# Sheet1.net
KiCad netlist of a schematic drawn in Altium Designer
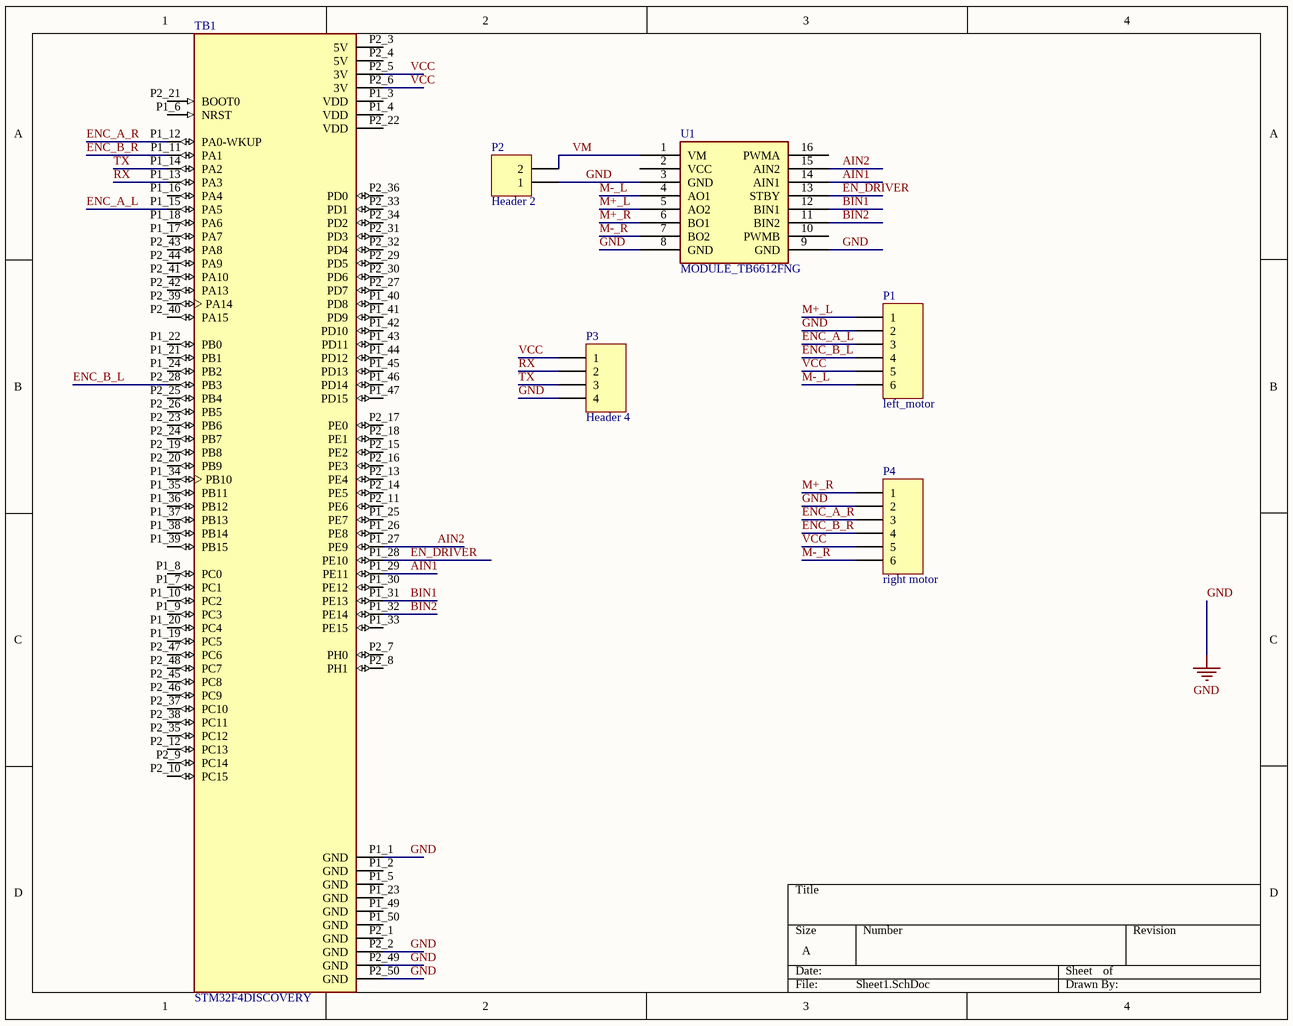
[diagram p0: Sheet1.SchDoc]

(export (version "E")
  (design (tool "Eeschema 10.0.6"))
  (components
    (comp (ref "P1")
      (value "left_motor")
      (footprint "HDR1X6")
      (description "Header, 6-Pin")
      (fields (field (name "PUBLISHER") "Altium Limited"))
      (libsource (lib "Miscellaneous Connectors") (part "Header 6"))
    )
    (comp (ref "P2")
      (value "Header 2")
      (footprint "HDR1X2")
      (description "Header, 2-Pin")
      (fields (field (name "PUBLISHER") "Altium Limited"))
      (libsource (lib "Miscellaneous Connectors") (part "Header 2"))
    )
    (comp (ref "P3")
      (value "Header 4")
      (footprint "HDR1X4")
      (description "Header, 4-Pin")
      (fields (field (name "PUBLISHER") "Altium Limited"))
      (libsource (lib "Miscellaneous Connectors") (part "Header 4"))
    )
    (comp (ref "P4")
      (value "right motor")
      (footprint "HDR1X6")
      (description "Header, 6-Pin")
      (fields (field (name "PUBLISHER") "Altium Limited"))
      (libsource (lib "Miscellaneous Connectors") (part "Header 6"))
    )
    (comp (ref "TB1")
      (value "STM32F4DISCOVERY")
      (footprint "MODULE_STM32F4DISCOVERY")
      (description "Development kit: ARM ST; pin strips, pin header; No.of")
      (libsource (lib "STM32F4DISCOVERY") (part "STM32F4DISCOVERY"))
    )
    (comp (ref "U1")
      (value "MODULE_TB6612FNG")
      (footprint "MODULE_TB6612FNG")
      (description "Module Dual Motor Driver 2.5-13.5V 3.2A Peak 21x18mm")
      (libsource (lib "Motor Drivers") (part "MODULE_TB6612FNG"))
    )
  )
  (nets
    (net (code "1") (name "/AIN1") (class "Default")
      (node (ref "TB1") (pin "P1_29") (pinfunction "PE11_P1_29") (pintype "bidirectional"))
      (node (ref "U1") (pin "14") (pinfunction "AIN1_14") (pintype "passive"))
    )
    (net (code "2") (name "/AIN2") (class "Default")
      (node (ref "TB1") (pin "P1_27") (pinfunction "PE9_P1_27") (pintype "bidirectional"))
      (node (ref "U1") (pin "15") (pinfunction "AIN2_15") (pintype "passive"))
    )
    (net (code "3") (name "/BIN1") (class "Default")
      (node (ref "TB1") (pin "P1_31") (pinfunction "PE13_P1_31") (pintype "bidirectional"))
      (node (ref "U1") (pin "12") (pinfunction "BIN1_12") (pintype "passive"))
    )
    (net (code "4") (name "/BIN2") (class "Default")
      (node (ref "TB1") (pin "P1_32") (pinfunction "PE14_P1_32") (pintype "bidirectional"))
      (node (ref "U1") (pin "11") (pinfunction "BIN2_11") (pintype "passive"))
    )
    (net (code "5") (name "/ENC_A_L") (class "Default")
      (node (ref "P1") (pin "3") (pinfunction "3_3") (pintype "passive"))
      (node (ref "TB1") (pin "P1_15") (pinfunction "PA5_P1_15") (pintype "bidirectional"))
    )
    (net (code "6") (name "/ENC_A_R") (class "Default")
      (node (ref "P4") (pin "3") (pinfunction "3_3") (pintype "passive"))
      (node (ref "TB1") (pin "P1_12") (pinfunction "PA0-WKUP_P1_12") (pintype "bidirectional"))
    )
    (net (code "7") (name "/ENC_B_L") (class "Default")
      (node (ref "P1") (pin "4") (pinfunction "4_4") (pintype "passive"))
      (node (ref "TB1") (pin "P2_28") (pinfunction "PB3_P2_28") (pintype "bidirectional"))
    )
    (net (code "8") (name "/ENC_B_R") (class "Default")
      (node (ref "P4") (pin "4") (pinfunction "4_4") (pintype "passive"))
      (node (ref "TB1") (pin "P1_11") (pinfunction "PA1_P1_11") (pintype "bidirectional"))
    )
    (net (code "9") (name "/EN_DRIVER") (class "Default")
      (node (ref "TB1") (pin "P1_28") (pinfunction "PE10_P1_28") (pintype "bidirectional"))
      (node (ref "U1") (pin "13") (pinfunction "STBY_13") (pintype "passive"))
    )
    (net (code "10") (name "/M+_L") (class "Default")
      (node (ref "P1") (pin "1") (pinfunction "1_1") (pintype "passive"))
      (node (ref "U1") (pin "5") (pinfunction "AO2_5") (pintype "passive"))
    )
    (net (code "11") (name "/M+_R") (class "Default")
      (node (ref "P4") (pin "1") (pinfunction "1_1") (pintype "passive"))
      (node (ref "U1") (pin "6") (pinfunction "BO1_6") (pintype "passive"))
    )
    (net (code "12") (name "/M-_L") (class "Default")
      (node (ref "P1") (pin "6") (pinfunction "6_6") (pintype "passive"))
      (node (ref "U1") (pin "4") (pinfunction "AO1_4") (pintype "passive"))
    )
    (net (code "13") (name "/M-_R") (class "Default")
      (node (ref "P4") (pin "6") (pinfunction "6_6") (pintype "passive"))
      (node (ref "U1") (pin "7") (pinfunction "BO2_7") (pintype "passive"))
    )
    (net (code "14") (name "/RX") (class "Default")
      (node (ref "P3") (pin "2") (pinfunction "2_2") (pintype "passive"))
      (node (ref "TB1") (pin "P1_13") (pinfunction "PA3_P1_13") (pintype "bidirectional"))
    )
    (net (code "15") (name "/TX") (class "Default")
      (node (ref "P3") (pin "3") (pinfunction "3_3") (pintype "passive"))
      (node (ref "TB1") (pin "P1_14") (pinfunction "PA2_P1_14") (pintype "bidirectional"))
    )
    (net (code "16") (name "/VCC") (class "Default")
      (node (ref "P1") (pin "5") (pinfunction "5_5") (pintype "passive"))
      (node (ref "P3") (pin "1") (pinfunction "1_1") (pintype "passive"))
      (node (ref "P4") (pin "5") (pinfunction "5_5") (pintype "passive"))
      (node (ref "TB1") (pin "P2_5") (pinfunction "3V_P2_5") (pintype "power_in"))
      (node (ref "TB1") (pin "P2_6") (pinfunction "3V_P2_6") (pintype "power_in"))
    )
    (net (code "17") (name "/VM") (class "Default")
      (node (ref "P2") (pin "2") (pinfunction "2_2") (pintype "passive"))
      (node (ref "U1") (pin "1") (pinfunction "VM_1") (pintype "passive"))
    )
    (net (code "18") (name "GND") (class "Default")
      (node (ref "P1") (pin "2") (pinfunction "2_2") (pintype "passive"))
      (node (ref "P2") (pin "1") (pinfunction "1_1") (pintype "passive"))
      (node (ref "P3") (pin "4") (pinfunction "4_4") (pintype "passive"))
      (node (ref "P4") (pin "2") (pinfunction "2_2") (pintype "passive"))
      (node (ref "TB1") (pin "P1_1") (pinfunction "GND_P1_1") (pintype "power_in"))
      (node (ref "TB1") (pin "P2_2") (pinfunction "GND_P2_2") (pintype "power_in"))
      (node (ref "TB1") (pin "P2_49") (pinfunction "GND_P2_49") (pintype "power_in"))
      (node (ref "TB1") (pin "P2_50") (pinfunction "GND_P2_50") (pintype "power_in"))
      (node (ref "U1") (pin "3") (pinfunction "GND_3") (pintype "passive"))
      (node (ref "U1") (pin "8") (pinfunction "GND_8") (pintype "passive"))
      (node (ref "U1") (pin "9") (pinfunction "GND_9") (pintype "passive"))
    )
    (net (code "19") (name "unconnected-(TB1-5V-PadP2_3)") (class "Default")
      (node (ref "TB1") (pin "P2_3") (pinfunction "5V_P2_3") (pintype "power_in"))
    )
    (net (code "20") (name "unconnected-(TB1-5V-PadP2_4)") (class "Default")
      (node (ref "TB1") (pin "P2_4") (pinfunction "5V_P2_4") (pintype "power_in"))
    )
    (net (code "21") (name "unconnected-(TB1-BOOT0-PadP2_21)") (class "Default")
      (node (ref "TB1") (pin "P2_21") (pinfunction "BOOT0_P2_21") (pintype "input"))
    )
    (net (code "22") (name "unconnected-(TB1-GND-PadP1_2)") (class "Default")
      (node (ref "TB1") (pin "P1_2") (pinfunction "GND_P1_2") (pintype "power_in"))
    )
    (net (code "23") (name "unconnected-(TB1-GND-PadP1_5)") (class "Default")
      (node (ref "TB1") (pin "P1_5") (pinfunction "GND_P1_5") (pintype "power_in"))
    )
    (net (code "24") (name "unconnected-(TB1-GND-PadP1_23)") (class "Default")
      (node (ref "TB1") (pin "P1_23") (pinfunction "GND_P1_23") (pintype "power_in"))
    )
    (net (code "25") (name "unconnected-(TB1-GND-PadP1_49)") (class "Default")
      (node (ref "TB1") (pin "P1_49") (pinfunction "GND_P1_49") (pintype "power_in"))
    )
    (net (code "26") (name "unconnected-(TB1-GND-PadP1_50)") (class "Default")
      (node (ref "TB1") (pin "P1_50") (pinfunction "GND_P1_50") (pintype "power_in"))
    )
    (net (code "27") (name "unconnected-(TB1-GND-PadP2_1)") (class "Default")
      (node (ref "TB1") (pin "P2_1") (pinfunction "GND_P2_1") (pintype "power_in"))
    )
    (net (code "28") (name "unconnected-(TB1-NRST-PadP1_6)") (class "Default")
      (node (ref "TB1") (pin "P1_6") (pinfunction "NRST_P1_6") (pintype "input"))
    )
    (net (code "29") (name "unconnected-(TB1-PA4-PadP1_16)") (class "Default")
      (node (ref "TB1") (pin "P1_16") (pinfunction "PA4_P1_16") (pintype "bidirectional"))
    )
    (net (code "30") (name "unconnected-(TB1-PA6-PadP1_18)") (class "Default")
      (node (ref "TB1") (pin "P1_18") (pinfunction "PA6_P1_18") (pintype "bidirectional"))
    )
    (net (code "31") (name "unconnected-(TB1-PA7-PadP1_17)") (class "Default")
      (node (ref "TB1") (pin "P1_17") (pinfunction "PA7_P1_17") (pintype "bidirectional"))
    )
    (net (code "32") (name "unconnected-(TB1-PA8-PadP2_43)") (class "Default")
      (node (ref "TB1") (pin "P2_43") (pinfunction "PA8_P2_43") (pintype "bidirectional"))
    )
    (net (code "33") (name "unconnected-(TB1-PA9-PadP2_44)") (class "Default")
      (node (ref "TB1") (pin "P2_44") (pinfunction "PA9_P2_44") (pintype "bidirectional"))
    )
    (net (code "34") (name "unconnected-(TB1-PA10-PadP2_41)") (class "Default")
      (node (ref "TB1") (pin "P2_41") (pinfunction "PA10_P2_41") (pintype "bidirectional"))
    )
    (net (code "35") (name "unconnected-(TB1-PA13-PadP2_42)") (class "Default")
      (node (ref "TB1") (pin "P2_42") (pinfunction "PA13_P2_42") (pintype "bidirectional"))
    )
    (net (code "36") (name "unconnected-(TB1-PA14-PadP2_39)") (class "Default")
      (node (ref "TB1") (pin "P2_39") (pinfunction "PA14_P2_39") (pintype "bidirectional"))
    )
    (net (code "37") (name "unconnected-(TB1-PA15-PadP2_40)") (class "Default")
      (node (ref "TB1") (pin "P2_40") (pinfunction "PA15_P2_40") (pintype "bidirectional"))
    )
    (net (code "38") (name "unconnected-(TB1-PB0-PadP1_22)") (class "Default")
      (node (ref "TB1") (pin "P1_22") (pinfunction "PB0_P1_22") (pintype "bidirectional"))
    )
    (net (code "39") (name "unconnected-(TB1-PB1-PadP1_21)") (class "Default")
      (node (ref "TB1") (pin "P1_21") (pinfunction "PB1_P1_21") (pintype "bidirectional"))
    )
    (net (code "40") (name "unconnected-(TB1-PB2-PadP1_24)") (class "Default")
      (node (ref "TB1") (pin "P1_24") (pinfunction "PB2_P1_24") (pintype "bidirectional"))
    )
    (net (code "41") (name "unconnected-(TB1-PB4-PadP2_25)") (class "Default")
      (node (ref "TB1") (pin "P2_25") (pinfunction "PB4_P2_25") (pintype "bidirectional"))
    )
    (net (code "42") (name "unconnected-(TB1-PB5-PadP2_26)") (class "Default")
      (node (ref "TB1") (pin "P2_26") (pinfunction "PB5_P2_26") (pintype "bidirectional"))
    )
    (net (code "43") (name "unconnected-(TB1-PB6-PadP2_23)") (class "Default")
      (node (ref "TB1") (pin "P2_23") (pinfunction "PB6_P2_23") (pintype "bidirectional"))
    )
    (net (code "44") (name "unconnected-(TB1-PB7-PadP2_24)") (class "Default")
      (node (ref "TB1") (pin "P2_24") (pinfunction "PB7_P2_24") (pintype "bidirectional"))
    )
    (net (code "45") (name "unconnected-(TB1-PB8-PadP2_19)") (class "Default")
      (node (ref "TB1") (pin "P2_19") (pinfunction "PB8_P2_19") (pintype "bidirectional"))
    )
    (net (code "46") (name "unconnected-(TB1-PB9-PadP2_20)") (class "Default")
      (node (ref "TB1") (pin "P2_20") (pinfunction "PB9_P2_20") (pintype "bidirectional"))
    )
    (net (code "47") (name "unconnected-(TB1-PB10-PadP1_34)") (class "Default")
      (node (ref "TB1") (pin "P1_34") (pinfunction "PB10_P1_34") (pintype "bidirectional"))
    )
    (net (code "48") (name "unconnected-(TB1-PB11-PadP1_35)") (class "Default")
      (node (ref "TB1") (pin "P1_35") (pinfunction "PB11_P1_35") (pintype "bidirectional"))
    )
    (net (code "49") (name "unconnected-(TB1-PB12-PadP1_36)") (class "Default")
      (node (ref "TB1") (pin "P1_36") (pinfunction "PB12_P1_36") (pintype "bidirectional"))
    )
    (net (code "50") (name "unconnected-(TB1-PB13-PadP1_37)") (class "Default")
      (node (ref "TB1") (pin "P1_37") (pinfunction "PB13_P1_37") (pintype "bidirectional"))
    )
    (net (code "51") (name "unconnected-(TB1-PB14-PadP1_38)") (class "Default")
      (node (ref "TB1") (pin "P1_38") (pinfunction "PB14_P1_38") (pintype "bidirectional"))
    )
    (net (code "52") (name "unconnected-(TB1-PB15-PadP1_39)") (class "Default")
      (node (ref "TB1") (pin "P1_39") (pinfunction "PB15_P1_39") (pintype "bidirectional"))
    )
    (net (code "53") (name "unconnected-(TB1-PC0-PadP1_8)") (class "Default")
      (node (ref "TB1") (pin "P1_8") (pinfunction "PC0_P1_8") (pintype "bidirectional"))
    )
    (net (code "54") (name "unconnected-(TB1-PC1-PadP1_7)") (class "Default")
      (node (ref "TB1") (pin "P1_7") (pinfunction "PC1_P1_7") (pintype "bidirectional"))
    )
    (net (code "55") (name "unconnected-(TB1-PC2-PadP1_10)") (class "Default")
      (node (ref "TB1") (pin "P1_10") (pinfunction "PC2_P1_10") (pintype "bidirectional"))
    )
    (net (code "56") (name "unconnected-(TB1-PC3-PadP1_9)") (class "Default")
      (node (ref "TB1") (pin "P1_9") (pinfunction "PC3_P1_9") (pintype "bidirectional"))
    )
    (net (code "57") (name "unconnected-(TB1-PC4-PadP1_20)") (class "Default")
      (node (ref "TB1") (pin "P1_20") (pinfunction "PC4_P1_20") (pintype "bidirectional"))
    )
    (net (code "58") (name "unconnected-(TB1-PC5-PadP1_19)") (class "Default")
      (node (ref "TB1") (pin "P1_19") (pinfunction "PC5_P1_19") (pintype "bidirectional"))
    )
    (net (code "59") (name "unconnected-(TB1-PC6-PadP2_47)") (class "Default")
      (node (ref "TB1") (pin "P2_47") (pinfunction "PC6_P2_47") (pintype "bidirectional"))
    )
    (net (code "60") (name "unconnected-(TB1-PC7-PadP2_48)") (class "Default")
      (node (ref "TB1") (pin "P2_48") (pinfunction "PC7_P2_48") (pintype "bidirectional"))
    )
    (net (code "61") (name "unconnected-(TB1-PC8-PadP2_45)") (class "Default")
      (node (ref "TB1") (pin "P2_45") (pinfunction "PC8_P2_45") (pintype "bidirectional"))
    )
    (net (code "62") (name "unconnected-(TB1-PC9-PadP2_46)") (class "Default")
      (node (ref "TB1") (pin "P2_46") (pinfunction "PC9_P2_46") (pintype "bidirectional"))
    )
    (net (code "63") (name "unconnected-(TB1-PC10-PadP2_37)") (class "Default")
      (node (ref "TB1") (pin "P2_37") (pinfunction "PC10_P2_37") (pintype "bidirectional"))
    )
    (net (code "64") (name "unconnected-(TB1-PC11-PadP2_38)") (class "Default")
      (node (ref "TB1") (pin "P2_38") (pinfunction "PC11_P2_38") (pintype "bidirectional"))
    )
    (net (code "65") (name "unconnected-(TB1-PC12-PadP2_35)") (class "Default")
      (node (ref "TB1") (pin "P2_35") (pinfunction "PC12_P2_35") (pintype "bidirectional"))
    )
    (net (code "66") (name "unconnected-(TB1-PC13-PadP2_12)") (class "Default")
      (node (ref "TB1") (pin "P2_12") (pinfunction "PC13_P2_12") (pintype "bidirectional"))
    )
    (net (code "67") (name "unconnected-(TB1-PC14-PadP2_9)") (class "Default")
      (node (ref "TB1") (pin "P2_9") (pinfunction "PC14_P2_9") (pintype "bidirectional"))
    )
    (net (code "68") (name "unconnected-(TB1-PC15-PadP2_10)") (class "Default")
      (node (ref "TB1") (pin "P2_10") (pinfunction "PC15_P2_10") (pintype "bidirectional"))
    )
    (net (code "69") (name "unconnected-(TB1-PD0-PadP2_36)") (class "Default")
      (node (ref "TB1") (pin "P2_36") (pinfunction "PD0_P2_36") (pintype "bidirectional"))
    )
    (net (code "70") (name "unconnected-(TB1-PD1-PadP2_33)") (class "Default")
      (node (ref "TB1") (pin "P2_33") (pinfunction "PD1_P2_33") (pintype "bidirectional"))
    )
    (net (code "71") (name "unconnected-(TB1-PD2-PadP2_34)") (class "Default")
      (node (ref "TB1") (pin "P2_34") (pinfunction "PD2_P2_34") (pintype "bidirectional"))
    )
    (net (code "72") (name "unconnected-(TB1-PD3-PadP2_31)") (class "Default")
      (node (ref "TB1") (pin "P2_31") (pinfunction "PD3_P2_31") (pintype "bidirectional"))
    )
    (net (code "73") (name "unconnected-(TB1-PD4-PadP2_32)") (class "Default")
      (node (ref "TB1") (pin "P2_32") (pinfunction "PD4_P2_32") (pintype "bidirectional"))
    )
    (net (code "74") (name "unconnected-(TB1-PD5-PadP2_29)") (class "Default")
      (node (ref "TB1") (pin "P2_29") (pinfunction "PD5_P2_29") (pintype "bidirectional"))
    )
    (net (code "75") (name "unconnected-(TB1-PD6-PadP2_30)") (class "Default")
      (node (ref "TB1") (pin "P2_30") (pinfunction "PD6_P2_30") (pintype "bidirectional"))
    )
    (net (code "76") (name "unconnected-(TB1-PD7-PadP2_27)") (class "Default")
      (node (ref "TB1") (pin "P2_27") (pinfunction "PD7_P2_27") (pintype "bidirectional"))
    )
    (net (code "77") (name "unconnected-(TB1-PD8-PadP1_40)") (class "Default")
      (node (ref "TB1") (pin "P1_40") (pinfunction "PD8_P1_40") (pintype "bidirectional"))
    )
    (net (code "78") (name "unconnected-(TB1-PD9-PadP1_41)") (class "Default")
      (node (ref "TB1") (pin "P1_41") (pinfunction "PD9_P1_41") (pintype "bidirectional"))
    )
    (net (code "79") (name "unconnected-(TB1-PD10-PadP1_42)") (class "Default")
      (node (ref "TB1") (pin "P1_42") (pinfunction "PD10_P1_42") (pintype "bidirectional"))
    )
    (net (code "80") (name "unconnected-(TB1-PD11-PadP1_43)") (class "Default")
      (node (ref "TB1") (pin "P1_43") (pinfunction "PD11_P1_43") (pintype "bidirectional"))
    )
    (net (code "81") (name "unconnected-(TB1-PD12-PadP1_44)") (class "Default")
      (node (ref "TB1") (pin "P1_44") (pinfunction "PD12_P1_44") (pintype "bidirectional"))
    )
    (net (code "82") (name "unconnected-(TB1-PD13-PadP1_45)") (class "Default")
      (node (ref "TB1") (pin "P1_45") (pinfunction "PD13_P1_45") (pintype "bidirectional"))
    )
    (net (code "83") (name "unconnected-(TB1-PD14-PadP1_46)") (class "Default")
      (node (ref "TB1") (pin "P1_46") (pinfunction "PD14_P1_46") (pintype "bidirectional"))
    )
    (net (code "84") (name "unconnected-(TB1-PD15-PadP1_47)") (class "Default")
      (node (ref "TB1") (pin "P1_47") (pinfunction "PD15_P1_47") (pintype "bidirectional"))
    )
    (net (code "85") (name "unconnected-(TB1-PE0-PadP2_17)") (class "Default")
      (node (ref "TB1") (pin "P2_17") (pinfunction "PE0_P2_17") (pintype "bidirectional"))
    )
    (net (code "86") (name "unconnected-(TB1-PE1-PadP2_18)") (class "Default")
      (node (ref "TB1") (pin "P2_18") (pinfunction "PE1_P2_18") (pintype "bidirectional"))
    )
    (net (code "87") (name "unconnected-(TB1-PE2-PadP2_15)") (class "Default")
      (node (ref "TB1") (pin "P2_15") (pinfunction "PE2_P2_15") (pintype "bidirectional"))
    )
    (net (code "88") (name "unconnected-(TB1-PE3-PadP2_16)") (class "Default")
      (node (ref "TB1") (pin "P2_16") (pinfunction "PE3_P2_16") (pintype "bidirectional"))
    )
    (net (code "89") (name "unconnected-(TB1-PE4-PadP2_13)") (class "Default")
      (node (ref "TB1") (pin "P2_13") (pinfunction "PE4_P2_13") (pintype "bidirectional"))
    )
    (net (code "90") (name "unconnected-(TB1-PE5-PadP2_14)") (class "Default")
      (node (ref "TB1") (pin "P2_14") (pinfunction "PE5_P2_14") (pintype "bidirectional"))
    )
    (net (code "91") (name "unconnected-(TB1-PE6-PadP2_11)") (class "Default")
      (node (ref "TB1") (pin "P2_11") (pinfunction "PE6_P2_11") (pintype "bidirectional"))
    )
    (net (code "92") (name "unconnected-(TB1-PE7-PadP1_25)") (class "Default")
      (node (ref "TB1") (pin "P1_25") (pinfunction "PE7_P1_25") (pintype "bidirectional"))
    )
    (net (code "93") (name "unconnected-(TB1-PE8-PadP1_26)") (class "Default")
      (node (ref "TB1") (pin "P1_26") (pinfunction "PE8_P1_26") (pintype "bidirectional"))
    )
    (net (code "94") (name "unconnected-(TB1-PE12-PadP1_30)") (class "Default")
      (node (ref "TB1") (pin "P1_30") (pinfunction "PE12_P1_30") (pintype "bidirectional"))
    )
    (net (code "95") (name "unconnected-(TB1-PE15-PadP1_33)") (class "Default")
      (node (ref "TB1") (pin "P1_33") (pinfunction "PE15_P1_33") (pintype "bidirectional"))
    )
    (net (code "96") (name "unconnected-(TB1-PH0-PadP2_7)") (class "Default")
      (node (ref "TB1") (pin "P2_7") (pinfunction "PH0_P2_7") (pintype "bidirectional"))
    )
    (net (code "97") (name "unconnected-(TB1-PH1-PadP2_8)") (class "Default")
      (node (ref "TB1") (pin "P2_8") (pinfunction "PH1_P2_8") (pintype "bidirectional"))
    )
    (net (code "98") (name "unconnected-(TB1-VDD-PadP1_3)") (class "Default")
      (node (ref "TB1") (pin "P1_3") (pinfunction "VDD_P1_3") (pintype "power_in"))
    )
    (net (code "99") (name "unconnected-(TB1-VDD-PadP1_4)") (class "Default")
      (node (ref "TB1") (pin "P1_4") (pinfunction "VDD_P1_4") (pintype "power_in"))
    )
    (net (code "100") (name "unconnected-(TB1-VDD-PadP2_22)") (class "Default")
      (node (ref "TB1") (pin "P2_22") (pinfunction "VDD_P2_22") (pintype "power_in"))
    )
    (net (code "101") (name "unconnected-(U1-PWMA-Pad16)") (class "Default")
      (node (ref "U1") (pin "16") (pinfunction "PWMA_16") (pintype "passive"))
    )
    (net (code "102") (name "unconnected-(U1-PWMB-Pad10)") (class "Default")
      (node (ref "U1") (pin "10") (pinfunction "PWMB_10") (pintype "passive"))
    )
    (net (code "103") (name "unconnected-(U1-VCC-Pad2)") (class "Default")
      (node (ref "U1") (pin "2") (pinfunction "VCC_2") (pintype "passive"))
    )
  )
)
